# EPCU.net
KiCad netlist of a schematic drawn in Altium Designer
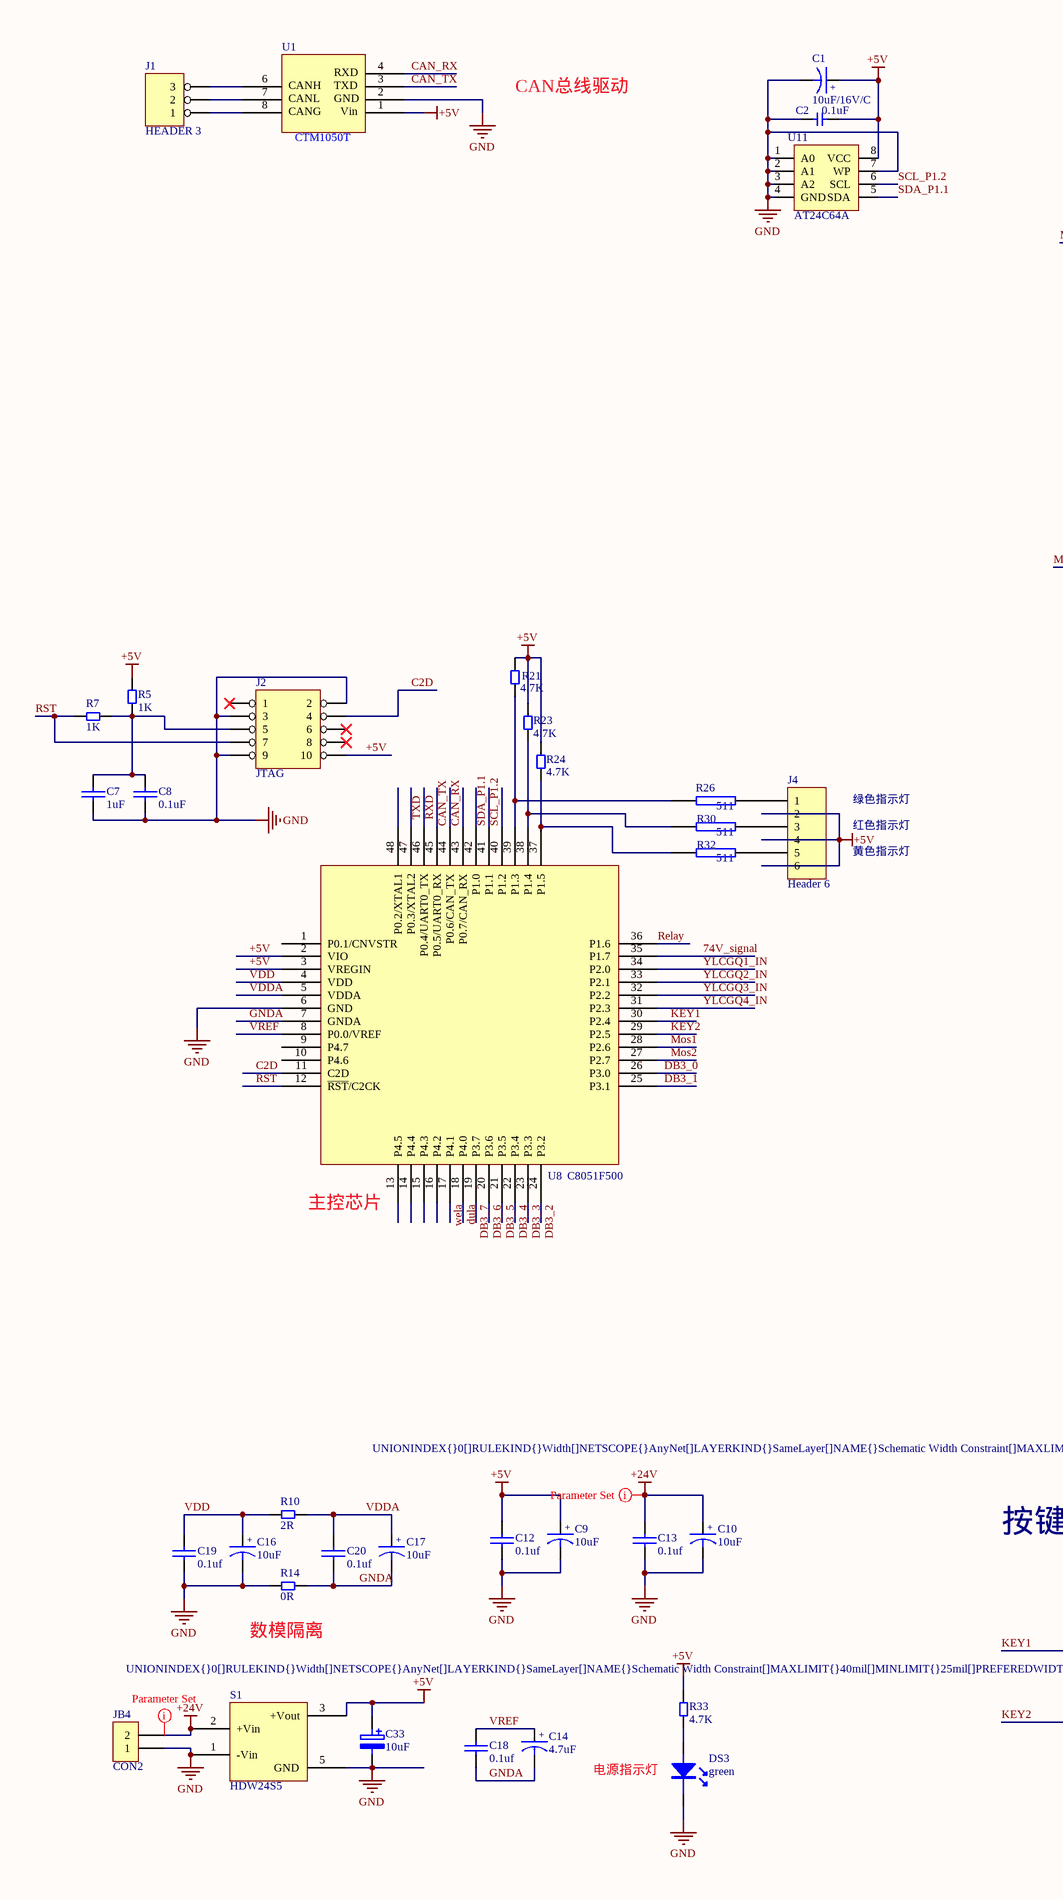
[diagram p0: EPCU.SchDoc, left]
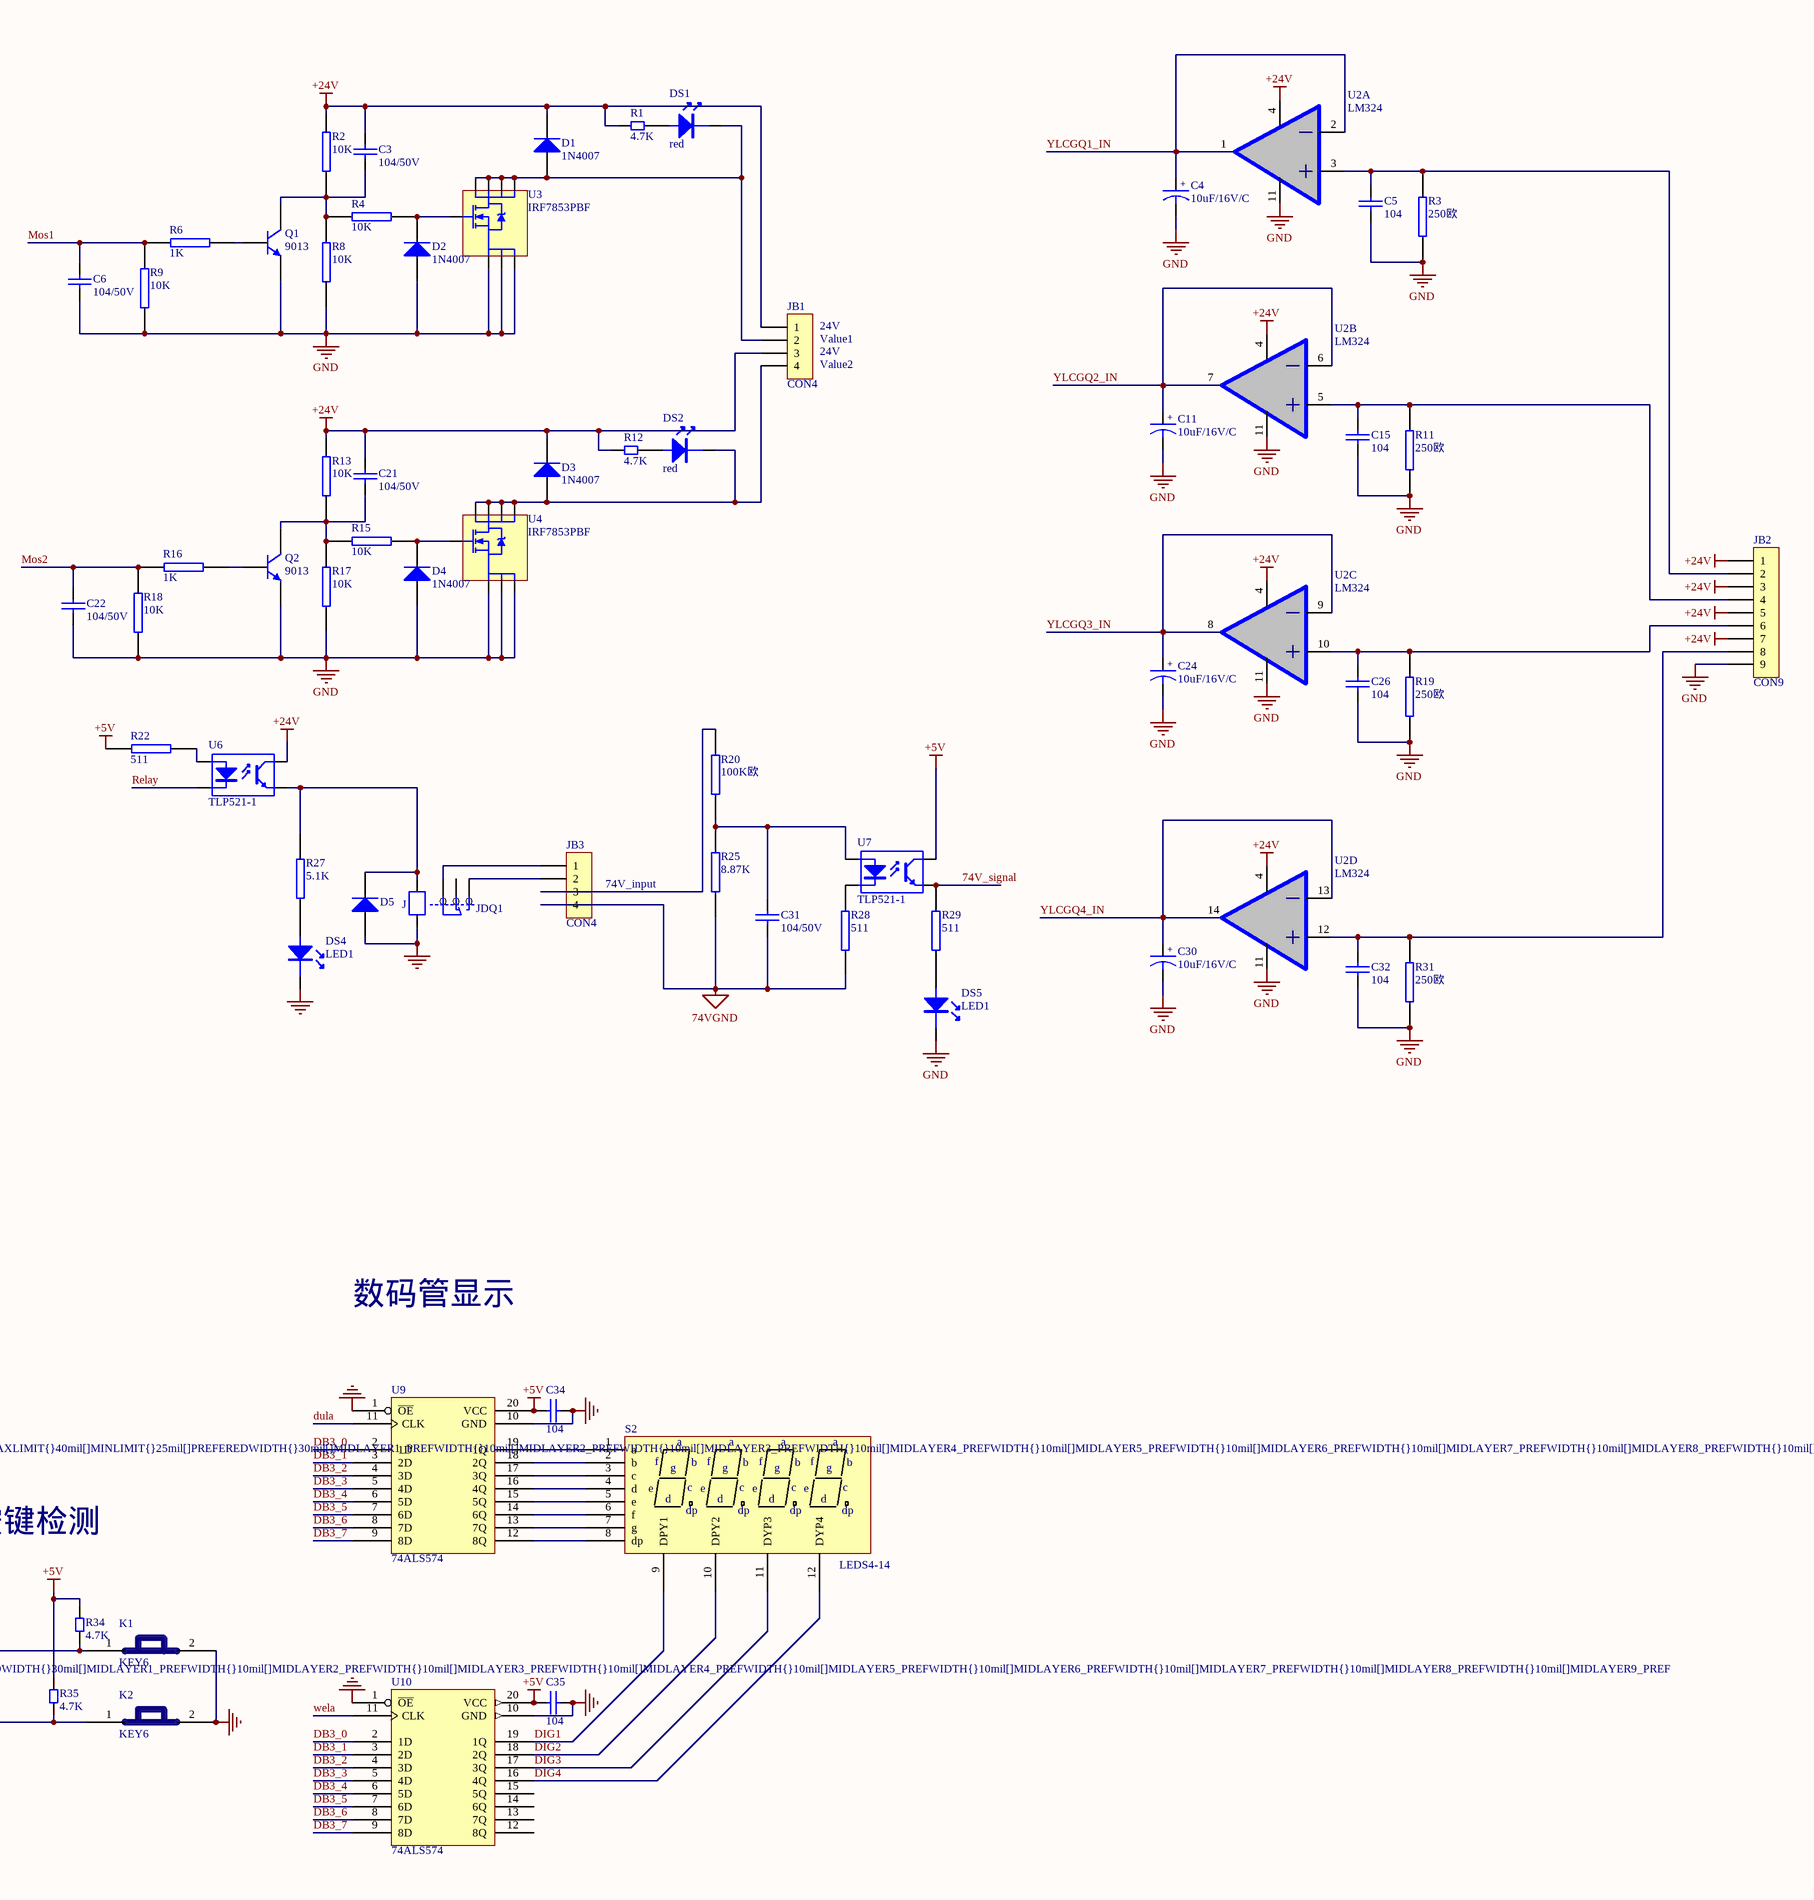
[diagram p1: EPCU.SchDoc, right]

(export (version "E")
  (design (tool "Eeschema 10.0.6"))
  (components
    (comp (ref "C1")
      (value "10uF/16V/C")
      (footprint "106E")
      (description "Capacitor")
      (libsource (lib "Backup of 13.02.20 XBX-APXSIRBASE4(change int0 and t2ex)") (part "CAPACITOR POL"))
    )
    (comp (ref "C2") (value "0.1uF") (footprint "0805") (libsource (lib "*") (part "CAP_S")))
    (comp (ref "C3")
      (value "104/50V")
      (footprint "0805")
      (description "Capacitor")
      (libsource (lib "PIS_JINAN") (part "CAP"))
    )
    (comp (ref "C4")
      (value "10uF/16V/C")
      (footprint "106E")
      (description "Capacitor")
      (libsource (lib "Backup of 13.02.20 XBX-APXSIRBASE4(change int0 and t2ex)") (part "CAPACITOR POL"))
    )
    (comp (ref "C5")
      (value "104")
      (footprint "0805")
      (description "Capacitor")
      (libsource (lib "PIS_JINAN") (part "CAP"))
    )
    (comp (ref "C6")
      (value "104/50V")
      (footprint "0805")
      (description "Capacitor")
      (libsource (lib "PIS_JINAN") (part "CAP"))
    )
    (comp (ref "C7")
      (value "1uF")
      (footprint "0805")
      (description "Capacitor")
      (libsource (lib "Backup of XBX-LINK") (part "CAP"))
    )
    (comp (ref "C8")
      (value "0.1uF")
      (footprint "0805")
      (description "Capacitor")
      (libsource (lib "Backup of XBX-LINK") (part "CAP"))
    )
    (comp (ref "C9")
      (value "10uF")
      (footprint "106E")
      (description "Capacitor")
      (libsource (lib "Backup of 13.02.20 XBX-APXSIRBASE4(change int0 and t2ex)") (part "CAPACITOR POL"))
    )
    (comp (ref "C10")
      (value "10uF")
      (footprint "106E")
      (description "Capacitor")
      (libsource (lib "Backup of 13.02.20 XBX-APXSIRBASE4(change int0 and t2ex)") (part "CAPACITOR POL"))
    )
    (comp (ref "C11")
      (value "10uF/16V/C")
      (footprint "106E")
      (description "Capacitor")
      (libsource (lib "Backup of 13.02.20 XBX-APXSIRBASE4(change int0 and t2ex)") (part "CAPACITOR POL"))
    )
    (comp (ref "C12")
      (value "0.1uf")
      (footprint "0805")
      (description "Capacitor")
      (libsource (lib "Backup of XBX-LINK") (part "CAP"))
    )
    (comp (ref "C13")
      (value "0.1uf")
      (footprint "0805")
      (description "Capacitor")
      (libsource (lib "Backup of XBX-LINK") (part "CAP"))
    )
    (comp (ref "C14")
      (value "4.7uF")
      (footprint "106E")
      (description "Capacitor")
      (libsource (lib "Backup of 13.02.20 XBX-APXSIRBASE4(change int0 and t2ex)") (part "CAPACITOR POL"))
    )
    (comp (ref "C15")
      (value "104")
      (footprint "0805")
      (description "Capacitor")
      (libsource (lib "PIS_JINAN") (part "CAP"))
    )
    (comp (ref "C16")
      (value "10uF")
      (footprint "106E")
      (description "Capacitor")
      (libsource (lib "Backup of 13.02.20 XBX-APXSIRBASE4(change int0 and t2ex)") (part "CAPACITOR POL"))
    )
    (comp (ref "C17")
      (value "10uF")
      (footprint "106E")
      (description "Capacitor")
      (libsource (lib "Backup of 13.02.20 XBX-APXSIRBASE4(change int0 and t2ex)") (part "CAPACITOR POL"))
    )
    (comp (ref "C18")
      (value "0.1uf")
      (footprint "0805")
      (description "Capacitor")
      (libsource (lib "Backup of XBX-LINK") (part "CAP"))
    )
    (comp (ref "C19")
      (value "0.1uf")
      (footprint "0805")
      (description "Capacitor")
      (libsource (lib "Backup of XBX-LINK") (part "CAP"))
    )
    (comp (ref "C20")
      (value "0.1uf")
      (footprint "0805")
      (description "Capacitor")
      (libsource (lib "Backup of XBX-LINK") (part "CAP"))
    )
    (comp (ref "C21")
      (value "104/50V")
      (footprint "0805")
      (description "Capacitor")
      (libsource (lib "PIS_JINAN") (part "CAP"))
    )
    (comp (ref "C22")
      (value "104/50V")
      (footprint "0805")
      (description "Capacitor")
      (libsource (lib "PIS_JINAN") (part "CAP"))
    )
    (comp (ref "C24")
      (value "10uF/16V/C")
      (footprint "106E")
      (description "Capacitor")
      (libsource (lib "Backup of 13.02.20 XBX-APXSIRBASE4(change int0 and t2ex)") (part "CAPACITOR POL"))
    )
    (comp (ref "C26")
      (value "104")
      (footprint "0805")
      (description "Capacitor")
      (libsource (lib "PIS_JINAN") (part "CAP"))
    )
    (comp (ref "C30")
      (value "10uF/16V/C")
      (footprint "106E")
      (description "Capacitor")
      (libsource (lib "Backup of 13.02.20 XBX-APXSIRBASE4(change int0 and t2ex)") (part "CAPACITOR POL"))
    )
    (comp (ref "C31")
      (value "104/50V")
      (footprint "0805")
      (description "Capacitor")
      (libsource (lib "PIS_JINAN") (part "CAP"))
    )
    (comp (ref "C32")
      (value "104")
      (footprint "0805")
      (description "Capacitor")
      (libsource (lib "PIS_JINAN") (part "CAP"))
    )
    (comp (ref "C33") (value "10uF") (footprint "RB.2/.4") (libsource (lib "*") (part "Pro12.tmp_22uF_5")))
    (comp (ref "C34")
      (value "104")
      (footprint "0805")
      (description "Capacitor")
      (libsource (lib "*") (part "CAP"))
    )
    (comp (ref "C35")
      (value "104")
      (footprint "0805")
      (description "Capacitor")
      (libsource (lib "*") (part "CAP"))
    )
    (comp (ref "D1")
      (value "1N4007")
      (footprint "DO-41")
      (description "1 Amp General Purpose Rectifier")
      (fields (field (name "PUBLISHER") "Altium Limited"))
      (libsource (lib "Miscellaneous Devices") (part "Diode 1N4007"))
    )
    (comp (ref "D2")
      (value "1N4007")
      (footprint "DO-41")
      (description "1 Amp General Purpose Rectifier")
      (fields (field (name "PUBLISHER") "Altium Limited"))
      (libsource (lib "Miscellaneous Devices") (part "Diode 1N4007"))
    )
    (comp (ref "D3")
      (value "1N4007")
      (footprint "DO-41")
      (description "1 Amp General Purpose Rectifier")
      (fields (field (name "PUBLISHER") "Altium Limited"))
      (libsource (lib "Miscellaneous Devices") (part "Diode 1N4007"))
    )
    (comp (ref "D4")
      (value "1N4007")
      (footprint "DO-41")
      (description "1 Amp General Purpose Rectifier")
      (fields (field (name "PUBLISHER") "Altium Limited"))
      (libsource (lib "Miscellaneous Devices") (part "Diode 1N4007"))
    )
    (comp (ref "D5")
      (value "Diode 1N4001")
      (footprint "DO-41")
      (description "1 Amp General Purpose Rectifier")
      (fields (field (name "PUBLISHER") "Altium Limited"))
      (libsource (lib "Miscellaneous Devices") (part "Diode 1N4001"))
    )
    (comp (ref "DS1") (value "red") (footprint "1206DIODE") (libsource (lib "Documents") (part "LED")))
    (comp (ref "DS2") (value "red") (footprint "1206DIODE") (libsource (lib "Documents") (part "LED")))
    (comp (ref "DS3") (value "green") (footprint "1206DIODE") (libsource (lib "Documents") (part "LED")))
    (comp (ref "DS4")
      (value "LED1")
      (footprint "1206DIODE")
      (description "1206")
      (libsource (lib "csu") (part "LED"))
    )
    (comp (ref "DS5")
      (value "LED1")
      (footprint "1206DIODE")
      (description "1206")
      (libsource (lib "csu") (part "LED"))
    )
    (comp (ref "J1")
      (value "HEADER 3")
      (footprint "254-3")
      (libsource (lib "Backup of XBX-LINK") (part "HEADER 3"))
    )
    (comp (ref "J2")
      (value "JTAG")
      (footprint "DC3-10P")
      (libsource (lib "Backup of XBX-LINK") (part "HEADER 5X2"))
    )
    (comp (ref "J4")
      (value "Header 6")
      (footprint "HDR1X6")
      (description "Header, 6-Pin")
      (fields (field (name "PUBLISHER") "Altium Limited"))
      (libsource (lib "Miscellaneous Connectors") (part "Header 6"))
    )
    (comp (ref "JB1")
      (value "CON4")
      (footprint "SIP4")
      (description "zhijiao")
      (libsource (lib "csu") (part "CON4"))
    )
    (comp (ref "JB2")
      (value "CON9")
      (footprint "SIP9")
      (description "connector")
      (libsource (lib "csu") (part "CON9"))
    )
    (comp (ref "JB3")
      (value "CON4")
      (footprint "SIP4")
      (description "zhijiao")
      (libsource (lib "csu") (part "CON4"))
    )
    (comp (ref "JB4") (value "CON2") (footprint "POWER2") (libsource (lib "csu") (part "CON2")))
    (comp (ref "JDQ1") (value "RELAY") (footprint "jidianqi_12VDC") (libsource (lib "csu") (part "RELAY")))
    (comp (ref "K1") (value "KEY6") (footprint "KEY6") (libsource (lib "ludebo_Library1") (part "KEY6")))
    (comp (ref "K2") (value "KEY6") (footprint "KEY6") (libsource (lib "ludebo_Library1") (part "KEY6")))
    (comp (ref "Q1")
      (value "9013")
      (footprint "TO-226-AA")
      (description "NPN Bipolar Transistor")
      (fields (field (name "PUBLISHER") "Altium Limited"))
      (libsource (lib "Miscellaneous Devices") (part "NPN"))
    )
    (comp (ref "Q2")
      (value "9013")
      (footprint "TO-226-AA")
      (description "NPN Bipolar Transistor")
      (fields (field (name "PUBLISHER") "Altium Limited"))
      (libsource (lib "Miscellaneous Devices") (part "NPN"))
    )
    (comp (ref "R1") (value "4.7K") (footprint "0805") (libsource (lib "Documents") (part "RES-S")))
    (comp (ref "R2") (value "10K") (footprint "0805") (libsource (lib "PIS_JINAN") (part "RES2")))
    (comp (ref "R3") (value "250欧") (footprint "AXIAL0.4") (libsource (lib "csu") (part "RES2")))
    (comp (ref "R4") (value "10K") (footprint "0805") (libsource (lib "PIS_JINAN") (part "RES2")))
    (comp (ref "R5") (value "1K") (footprint "0805") (libsource (lib "Backup of XBX-LINK") (part "RES-S")))
    (comp (ref "R6") (value "1K") (footprint "0805") (libsource (lib "PIS_JINAN") (part "RES2")))
    (comp (ref "R7") (value "1K") (footprint "0805") (libsource (lib "Backup of XBX-LINK") (part "RES-S")))
    (comp (ref "R8") (value "10K") (footprint "0805") (libsource (lib "PIS_JINAN") (part "RES2")))
    (comp (ref "R9") (value "10K") (footprint "0805") (libsource (lib "PIS_JINAN") (part "RES2")))
    (comp (ref "R10") (value "2R") (footprint "0805") (libsource (lib "Documents") (part "RES-S")))
    (comp (ref "R11") (value "250欧") (footprint "AXIAL0.4") (libsource (lib "csu") (part "RES2")))
    (comp (ref "R12") (value "4.7K") (footprint "0805") (libsource (lib "Documents") (part "RES-S")))
    (comp (ref "R13") (value "10K") (footprint "0805") (libsource (lib "PIS_JINAN") (part "RES2")))
    (comp (ref "R14") (value "0R") (footprint "0805") (libsource (lib "Documents") (part "RES-S")))
    (comp (ref "R15") (value "10K") (footprint "0805") (libsource (lib "PIS_JINAN") (part "RES2")))
    (comp (ref "R16") (value "1K") (footprint "0805") (libsource (lib "PIS_JINAN") (part "RES2")))
    (comp (ref "R17") (value "10K") (footprint "0805") (libsource (lib "PIS_JINAN") (part "RES2")))
    (comp (ref "R18") (value "10K") (footprint "0805") (libsource (lib "PIS_JINAN") (part "RES2")))
    (comp (ref "R19") (value "250欧") (footprint "AXIAL0.4") (libsource (lib "csu") (part "RES2")))
    (comp (ref "R20") (value "100K欧") (footprint "AXIAL0.4") (libsource (lib "csu") (part "RES2")))
    (comp (ref "R21") (value "4.7K") (footprint "0805") (libsource (lib "Documents") (part "RES-S")))
    (comp (ref "R22") (value "511") (footprint "0805") (libsource (lib "PIS_JINAN") (part "RES2")))
    (comp (ref "R23") (value "4.7K") (footprint "0805") (libsource (lib "Documents") (part "RES-S")))
    (comp (ref "R24") (value "4.7K") (footprint "0805") (libsource (lib "Documents") (part "RES-S")))
    (comp (ref "R25") (value "8.87K") (footprint "AXIAL0.4") (libsource (lib "csu") (part "RES2")))
    (comp (ref "R26") (value "511") (footprint "0805") (libsource (lib "PIS_JINAN") (part "RES2")))
    (comp (ref "R27") (value "5.1K") (footprint "0805") (libsource (lib "PIS_JINAN") (part "RES2")))
    (comp (ref "R28") (value "511") (footprint "0805") (libsource (lib "PIS_JINAN") (part "RES2")))
    (comp (ref "R29") (value "511") (footprint "1206DIODE") (libsource (lib "PIS_JINAN") (part "RES2")))
    (comp (ref "R30") (value "511") (footprint "0805") (libsource (lib "PIS_JINAN") (part "RES2")))
    (comp (ref "R31") (value "250欧") (footprint "AXIAL0.4") (libsource (lib "csu") (part "RES2")))
    (comp (ref "R32") (value "511") (footprint "0805") (libsource (lib "PIS_JINAN") (part "RES2")))
    (comp (ref "R33") (value "4.7K") (footprint "0805") (libsource (lib "Documents") (part "RES-S")))
    (comp (ref "R34") (value "4.7K") (footprint "0805") (libsource (lib "Documents") (part "RES-S")))
    (comp (ref "R35") (value "4.7K") (footprint "0805") (libsource (lib "Documents") (part "RES-S")))
    (comp (ref "S1") (value "HDW24S5") (footprint "HDW24S5") (libsource (lib "csu") (part "HDW24S5")))
    (comp (ref "S2")
      (value "LEDS4-14")
      (footprint "LEDS4-14")
      (libsource (lib "ludebo_Library1") (part "LEDS4-14"))
    )
    (comp (ref "U1") (value "~") (footprint "CYM1050T") (libsource (lib "csu") (part "CTM1050T")))
    (comp (ref "U2") (value "LM324") (footprint "lm324") (libsource (lib "csu") (part "LM324")))
    (comp (ref "U3") (value "IRF7853PBF") (footprint "SOP-8") (libsource (lib "csu") (part "IRF7853PBF")))
    (comp (ref "U4") (value "IRF7853PBF") (footprint "SO-8") (libsource (lib "csu") (part "IRF7853PBF")))
    (comp (ref "U6") (value "TLP521-1") (footprint "TLP521-1") (libsource (lib "csu") (part "TLP521-1")))
    (comp (ref "U7") (value "TLP521-1") (footprint "TLP521-1") (libsource (lib "csu") (part "TLP521-1")))
    (comp (ref "U8")
      (value "C8051F500")
      (footprint "TQFP-48")
      (libsource (lib "Backup of XBX-LINK") (part "C8051F500/1/4/5"))
    )
    (comp (ref "U9") (value "74ALS574") (footprint "SOL-20") (libsource (lib "*") (part "74ALS574")))
    (comp (ref "U10") (value "74ALS574") (footprint "SOL-20") (libsource (lib "*") (part "74ALS574")))
    (comp (ref "U11") (value "AT24C64A") (footprint "SO-8") (libsource (lib "*") (part "AT24CXXA")))
  )
  (nets
    (net (code "1") (name "+5V") (class "Default")
      (node (ref "C1") (pin "1") (pinfunction "1_1") (pintype "passive"))
      (node (ref "C12") (pin "2") (pinfunction "2_2") (pintype "passive"))
      (node (ref "C2") (pin "2") (pinfunction "2_2") (pintype "passive"))
      (node (ref "C33") (pin "1") (pintype "passive"))
      (node (ref "C34") (pin "1") (pinfunction "1_1") (pintype "passive"))
      (node (ref "C35") (pin "1") (pinfunction "1_1") (pintype "passive"))
      (node (ref "C9") (pin "1") (pinfunction "1_1") (pintype "passive"))
      (node (ref "J2") (pin "10") (pinfunction "10_10") (pintype "passive"))
      (node (ref "J4") (pin "2") (pinfunction "2_2") (pintype "passive"))
      (node (ref "J4") (pin "4") (pinfunction "4_4") (pintype "passive"))
      (node (ref "J4") (pin "6") (pinfunction "6_6") (pintype "passive"))
      (node (ref "R21") (pin "2") (pinfunction "2_2") (pintype "passive"))
      (node (ref "R22") (pin "2") (pinfunction "2_2") (pintype "passive"))
      (node (ref "R23") (pin "1") (pinfunction "1_1") (pintype "passive"))
      (node (ref "R24") (pin "1") (pinfunction "1_1") (pintype "passive"))
      (node (ref "R33") (pin "1") (pinfunction "1_1") (pintype "passive"))
      (node (ref "R34") (pin "1") (pinfunction "1_1") (pintype "passive"))
      (node (ref "R35") (pin "2") (pinfunction "2_2") (pintype "passive"))
      (node (ref "R5") (pin "1") (pinfunction "1_1") (pintype "passive"))
      (node (ref "S1") (pin "3") (pinfunction "+Vout_3") (pintype "passive"))
      (node (ref "U1") (pin "1") (pinfunction "1_1") (pintype "passive"))
      (node (ref "U10") (pin "20") (pinfunction "VCC_20") (pintype "output"))
      (node (ref "U11") (pin "8") (pinfunction "VCC_8") (pintype "passive"))
      (node (ref "U7") (pin "4") (pinfunction "C_4") (pintype "passive"))
      (node (ref "U8") (pin "2") (pinfunction "VIO_2") (pintype "passive"))
      (node (ref "U8") (pin "3") (pinfunction "VREGIN_3") (pintype "passive"))
      (node (ref "U9") (pin "20") (pinfunction "VCC_20") (pintype "output"))
    )
    (net (code "2") (name "+24V") (class "Default")
      (node (ref "C10") (pin "1") (pinfunction "1_1") (pintype "passive"))
      (node (ref "C13") (pin "2") (pinfunction "2_2") (pintype "passive"))
      (node (ref "C21") (pin "1") (pinfunction "1_1") (pintype "passive"))
      (node (ref "C3") (pin "1") (pinfunction "1_1") (pintype "passive"))
      (node (ref "D1") (pin "2") (pinfunction "K_2") (pintype "passive"))
      (node (ref "D3") (pin "2") (pinfunction "K_2") (pintype "passive"))
      (node (ref "JB1") (pin "1") (pinfunction "1_1") (pintype "passive"))
      (node (ref "JB1") (pin "3") (pinfunction "3_3") (pintype "passive"))
      (node (ref "JB2") (pin "1") (pinfunction "1_1") (pintype "passive"))
      (node (ref "JB2") (pin "3") (pinfunction "3_3") (pintype "passive"))
      (node (ref "JB2") (pin "5") (pinfunction "5_5") (pintype "passive"))
      (node (ref "JB2") (pin "7") (pinfunction "7_7") (pintype "passive"))
      (node (ref "JB4") (pin "2") (pinfunction "2_2") (pintype "passive"))
      (node (ref "R1") (pin "2") (pinfunction "2_2") (pintype "passive"))
      (node (ref "R12") (pin "2") (pinfunction "2_2") (pintype "passive"))
      (node (ref "R13") (pin "2") (pinfunction "2_2") (pintype "passive"))
      (node (ref "R2") (pin "2") (pinfunction "2_2") (pintype "passive"))
      (node (ref "S1") (pin "2") (pinfunction "+Vin_2") (pintype "passive"))
      (node (ref "U2") (pin "4") (pinfunction "4_4") (pintype "passive"))
      (node (ref "U6") (pin "4") (pinfunction "C_4") (pintype "passive"))
    )
    (net (code "3") (name "/74V_signal") (class "Default")
      (node (ref "R29") (pin "2") (pinfunction "2_2") (pintype "passive"))
      (node (ref "U7") (pin "3") (pinfunction "E_3") (pintype "passive"))
      (node (ref "U8") (pin "35") (pinfunction "P1.7_35") (pintype "passive"))
    )
    (net (code "4") (name "/C2D") (class "Default")
      (node (ref "J2") (pin "4") (pinfunction "4_4") (pintype "passive"))
      (node (ref "U8") (pin "11") (pinfunction "C2D_11") (pintype "passive"))
    )
    (net (code "5") (name "/CAN_RX") (class "Default")
      (node (ref "U1") (pin "4") (pinfunction "4_4") (pintype "passive"))
      (node (ref "U8") (pin "43") (pinfunction "P0.7/CAN_RX_43") (pintype "passive"))
    )
    (net (code "6") (name "/CAN_TX") (class "Default")
      (node (ref "U1") (pin "3") (pinfunction "3_3") (pintype "passive"))
      (node (ref "U8") (pin "44") (pinfunction "P0.6/CAN_TX_44") (pintype "passive"))
    )
    (net (code "7") (name "/DB3_0") (class "Default")
      (node (ref "U10") (pin "2") (pinfunction "1D_2") (pintype "passive"))
      (node (ref "U8") (pin "26") (pinfunction "P3.0_26") (pintype "passive"))
      (node (ref "U9") (pin "2") (pinfunction "1D_2") (pintype "passive"))
    )
    (net (code "8") (name "/DB3_1") (class "Default")
      (node (ref "U10") (pin "3") (pinfunction "2D_3") (pintype "passive"))
      (node (ref "U8") (pin "25") (pinfunction "P3.1_25") (pintype "passive"))
      (node (ref "U9") (pin "3") (pinfunction "2D_3") (pintype "passive"))
    )
    (net (code "9") (name "/DB3_2") (class "Default")
      (node (ref "U10") (pin "4") (pinfunction "3D_4") (pintype "passive"))
      (node (ref "U8") (pin "24") (pinfunction "P3.2_24") (pintype "passive"))
      (node (ref "U9") (pin "4") (pinfunction "3D_4") (pintype "passive"))
    )
    (net (code "10") (name "/DB3_3") (class "Default")
      (node (ref "U10") (pin "5") (pinfunction "4D_5") (pintype "passive"))
      (node (ref "U8") (pin "23") (pinfunction "P3.3_23") (pintype "passive"))
      (node (ref "U9") (pin "5") (pinfunction "4D_5") (pintype "passive"))
    )
    (net (code "11") (name "/DB3_4") (class "Default")
      (node (ref "U10") (pin "6") (pinfunction "5D_6") (pintype "passive"))
      (node (ref "U8") (pin "22") (pinfunction "P3.4_22") (pintype "passive"))
      (node (ref "U9") (pin "6") (pinfunction "5D_6") (pintype "passive"))
    )
    (net (code "12") (name "/DB3_5") (class "Default")
      (node (ref "U10") (pin "7") (pinfunction "6D_7") (pintype "passive"))
      (node (ref "U8") (pin "21") (pinfunction "P3.5_21") (pintype "passive"))
      (node (ref "U9") (pin "7") (pinfunction "6D_7") (pintype "passive"))
    )
    (net (code "13") (name "/DB3_6") (class "Default")
      (node (ref "U10") (pin "8") (pinfunction "7D_8") (pintype "passive"))
      (node (ref "U8") (pin "20") (pinfunction "P3.6_20") (pintype "passive"))
      (node (ref "U9") (pin "8") (pinfunction "7D_8") (pintype "passive"))
    )
    (net (code "14") (name "/DB3_7") (class "Default")
      (node (ref "U10") (pin "9") (pinfunction "8D_9") (pintype "passive"))
      (node (ref "U8") (pin "19") (pinfunction "P3.7_19") (pintype "passive"))
      (node (ref "U9") (pin "9") (pinfunction "8D_9") (pintype "passive"))
    )
    (net (code "15") (name "/DIG1") (class "Default")
      (node (ref "S2") (pin "9") (pinfunction "DPY1_9") (pintype "passive"))
      (node (ref "U10") (pin "19") (pinfunction "1Q_19") (pintype "passive"))
    )
    (net (code "16") (name "/DIG2") (class "Default")
      (node (ref "S2") (pin "10") (pinfunction "DPY2_10") (pintype "passive"))
      (node (ref "U10") (pin "18") (pinfunction "2Q_18") (pintype "passive"))
    )
    (net (code "17") (name "/DIG3") (class "Default")
      (node (ref "S2") (pin "11") (pinfunction "DYP3_11") (pintype "passive"))
      (node (ref "U10") (pin "17") (pinfunction "3Q_17") (pintype "passive"))
    )
    (net (code "18") (name "/DIG4") (class "Default")
      (node (ref "S2") (pin "12") (pinfunction "DYP4_12") (pintype "passive"))
      (node (ref "U10") (pin "16") (pinfunction "4Q_16") (pintype "passive"))
    )
    (net (code "19") (name "/GNDA") (class "Default")
      (node (ref "C14") (pin "2") (pinfunction "2_2") (pintype "passive"))
      (node (ref "C17") (pin "2") (pinfunction "2_2") (pintype "passive"))
      (node (ref "C18") (pin "1") (pinfunction "1_1") (pintype "passive"))
      (node (ref "C20") (pin "1") (pinfunction "1_1") (pintype "passive"))
      (node (ref "R14") (pin "1") (pinfunction "1_1") (pintype "passive"))
      (node (ref "U8") (pin "7") (pinfunction "GNDA_7") (pintype "passive"))
    )
    (net (code "20") (name "/KEY1") (class "Default")
      (node (ref "K1") (pin "1") (pinfunction "1_1") (pintype "passive"))
      (node (ref "R34") (pin "2") (pinfunction "2_2") (pintype "passive"))
      (node (ref "U8") (pin "30") (pinfunction "P2.4_30") (pintype "passive"))
    )
    (net (code "21") (name "/KEY2") (class "Default")
      (node (ref "K2") (pin "1") (pinfunction "1_1") (pintype "passive"))
      (node (ref "R35") (pin "1") (pinfunction "1_1") (pintype "passive"))
      (node (ref "U8") (pin "29") (pinfunction "P2.5_29") (pintype "passive"))
    )
    (net (code "22") (name "/Mos1") (class "Default")
      (node (ref "C6") (pin "1") (pinfunction "1_1") (pintype "passive"))
      (node (ref "R6") (pin "1") (pinfunction "1_1") (pintype "passive"))
      (node (ref "R9") (pin "2") (pinfunction "2_2") (pintype "passive"))
      (node (ref "U8") (pin "28") (pinfunction "P2.6_28") (pintype "passive"))
    )
    (net (code "23") (name "/Mos2") (class "Default")
      (node (ref "C22") (pin "1") (pinfunction "1_1") (pintype "passive"))
      (node (ref "R16") (pin "1") (pinfunction "1_1") (pintype "passive"))
      (node (ref "R18") (pin "2") (pinfunction "2_2") (pintype "passive"))
      (node (ref "U8") (pin "27") (pinfunction "P2.7_27") (pintype "passive"))
    )
    (net (code "24") (name "/RST") (class "Default")
      (node (ref "J2") (pin "7") (pinfunction "7_7") (pintype "passive"))
      (node (ref "R7") (pin "2") (pinfunction "2_2") (pintype "passive"))
      (node (ref "U8") (pin "12") (pinfunction "~{RST}/C2CK_12") (pintype "passive"))
    )
    (net (code "25") (name "/RXD") (class "Default")
      (node (ref "U8") (pin "45") (pinfunction "P0.5/UART0_RX_45") (pintype "passive"))
    )
    (net (code "26") (name "/Relay") (class "Default")
      (node (ref "U6") (pin "2") (pinfunction "K_2") (pintype "passive"))
      (node (ref "U8") (pin "36") (pinfunction "P1.6_36") (pintype "passive"))
    )
    (net (code "27") (name "/SCL_P1.2") (class "Default")
      (node (ref "U11") (pin "6") (pinfunction "SCL_6") (pintype "passive"))
      (node (ref "U8") (pin "40") (pinfunction "P1.2_40") (pintype "passive"))
    )
    (net (code "28") (name "/SDA_P1.1") (class "Default")
      (node (ref "U11") (pin "5") (pinfunction "SDA_5") (pintype "passive"))
      (node (ref "U8") (pin "41") (pinfunction "P1.1_41") (pintype "passive"))
    )
    (net (code "29") (name "/TXD") (class "Default")
      (node (ref "U8") (pin "46") (pinfunction "P0.4/UART0_TX_46") (pintype "passive"))
    )
    (net (code "30") (name "/VDD") (class "Default")
      (node (ref "C16") (pin "1") (pinfunction "1_1") (pintype "passive"))
      (node (ref "C19") (pin "2") (pinfunction "2_2") (pintype "passive"))
      (node (ref "R10") (pin "2") (pinfunction "2_2") (pintype "passive"))
      (node (ref "U8") (pin "4") (pinfunction "VDD_4") (pintype "passive"))
    )
    (net (code "31") (name "/VDDA") (class "Default")
      (node (ref "C17") (pin "1") (pinfunction "1_1") (pintype "passive"))
      (node (ref "C20") (pin "2") (pinfunction "2_2") (pintype "passive"))
      (node (ref "R10") (pin "1") (pinfunction "1_1") (pintype "passive"))
      (node (ref "U8") (pin "5") (pinfunction "VDDA_5") (pintype "passive"))
    )
    (net (code "32") (name "/VREF") (class "Default")
      (node (ref "C14") (pin "1") (pinfunction "1_1") (pintype "passive"))
      (node (ref "C18") (pin "2") (pinfunction "2_2") (pintype "passive"))
      (node (ref "U8") (pin "8") (pinfunction "P0.0/VREF_8") (pintype "passive"))
    )
    (net (code "33") (name "/YLCGQ1_IN") (class "Default")
      (node (ref "C4") (pin "1") (pinfunction "1_1") (pintype "passive"))
      (node (ref "U2") (pin "1") (pinfunction "1_1") (pintype "passive"))
      (node (ref "U2") (pin "2") (pinfunction "2_2") (pintype "passive"))
      (node (ref "U8") (pin "34") (pinfunction "P2.0_34") (pintype "passive"))
    )
    (net (code "34") (name "/YLCGQ2_IN") (class "Default")
      (node (ref "C11") (pin "1") (pinfunction "1_1") (pintype "passive"))
      (node (ref "U2") (pin "6") (pinfunction "6_6") (pintype "passive"))
      (node (ref "U2") (pin "7") (pinfunction "7_7") (pintype "passive"))
      (node (ref "U8") (pin "33") (pinfunction "P2.1_33") (pintype "passive"))
    )
    (net (code "35") (name "/YLCGQ3_IN") (class "Default")
      (node (ref "C24") (pin "1") (pinfunction "1_1") (pintype "passive"))
      (node (ref "U2") (pin "8") (pinfunction "8_8") (pintype "passive"))
      (node (ref "U2") (pin "9") (pinfunction "9_9") (pintype "passive"))
      (node (ref "U8") (pin "32") (pinfunction "P2.2_32") (pintype "passive"))
    )
    (net (code "36") (name "/YLCGQ4_IN") (class "Default")
      (node (ref "C30") (pin "1") (pinfunction "1_1") (pintype "passive"))
      (node (ref "U2") (pin "13") (pinfunction "13_13") (pintype "passive"))
      (node (ref "U2") (pin "14") (pinfunction "14_14") (pintype "passive"))
      (node (ref "U8") (pin "31") (pinfunction "P2.3_31") (pintype "passive"))
    )
    (net (code "37") (name "/dula") (class "Default")
      (node (ref "U8") (pin "18") (pinfunction "P4.0_18") (pintype "passive"))
      (node (ref "U9") (pin "11") (pinfunction "CLK_11") (pintype "passive"))
    )
    (net (code "38") (name "/wela") (class "Default")
      (node (ref "U10") (pin "11") (pinfunction "CLK_11") (pintype "passive"))
      (node (ref "U8") (pin "17") (pinfunction "P4.1_17") (pintype "passive"))
    )
    (net (code "39") (name "74VGND") (class "Default")
      (node (ref "C31") (pin "2") (pinfunction "2_2") (pintype "passive"))
      (node (ref "JB3") (pin "4") (pinfunction "4_4") (pintype "passive"))
      (node (ref "R25") (pin "1") (pinfunction "1_1") (pintype "passive"))
      (node (ref "R28") (pin "2") (pinfunction "2_2") (pintype "passive"))
    )
    (net (code "40") (name "GND") (class "Default")
      (node (ref "C1") (pin "2") (pinfunction "2_2") (pintype "passive"))
      (node (ref "C10") (pin "2") (pinfunction "2_2") (pintype "passive"))
      (node (ref "C11") (pin "2") (pinfunction "2_2") (pintype "passive"))
      (node (ref "C12") (pin "1") (pinfunction "1_1") (pintype "passive"))
      (node (ref "C13") (pin "1") (pinfunction "1_1") (pintype "passive"))
      (node (ref "C15") (pin "2") (pinfunction "2_2") (pintype "passive"))
      (node (ref "C16") (pin "2") (pinfunction "2_2") (pintype "passive"))
      (node (ref "C19") (pin "1") (pinfunction "1_1") (pintype "passive"))
      (node (ref "C2") (pin "1") (pinfunction "1_1") (pintype "passive"))
      (node (ref "C22") (pin "2") (pinfunction "2_2") (pintype "passive"))
      (node (ref "C24") (pin "2") (pinfunction "2_2") (pintype "passive"))
      (node (ref "C26") (pin "2") (pinfunction "2_2") (pintype "passive"))
      (node (ref "C30") (pin "2") (pinfunction "2_2") (pintype "passive"))
      (node (ref "C32") (pin "2") (pinfunction "2_2") (pintype "passive"))
      (node (ref "C33") (pin "2") (pintype "passive"))
      (node (ref "C34") (pin "2") (pinfunction "2_2") (pintype "passive"))
      (node (ref "C35") (pin "2") (pinfunction "2_2") (pintype "passive"))
      (node (ref "C4") (pin "2") (pinfunction "2_2") (pintype "passive"))
      (node (ref "C5") (pin "2") (pinfunction "2_2") (pintype "passive"))
      (node (ref "C6") (pin "2") (pinfunction "2_2") (pintype "passive"))
      (node (ref "C7") (pin "1") (pinfunction "1_1") (pintype "passive"))
      (node (ref "C8") (pin "1") (pinfunction "1_1") (pintype "passive"))
      (node (ref "C9") (pin "2") (pinfunction "2_2") (pintype "passive"))
      (node (ref "D2") (pin "1") (pinfunction "A_1") (pintype "passive"))
      (node (ref "D4") (pin "1") (pinfunction "A_1") (pintype "passive"))
      (node (ref "D5") (pin "1") (pinfunction "A_1") (pintype "passive"))
      (node (ref "DS3") (pin "2") (pinfunction "K_2") (pintype "passive"))
      (node (ref "DS4") (pin "2") (pinfunction "K_2") (pintype "passive"))
      (node (ref "DS5") (pin "2") (pinfunction "K_2") (pintype "passive"))
      (node (ref "J2") (pin "2") (pinfunction "2_2") (pintype "passive"))
      (node (ref "J2") (pin "3") (pinfunction "3_3") (pintype "passive"))
      (node (ref "J2") (pin "9") (pinfunction "9_9") (pintype "passive"))
      (node (ref "JB2") (pin "9") (pinfunction "9_9") (pintype "passive"))
      (node (ref "JB4") (pin "1") (pinfunction "1_1") (pintype "passive"))
      (node (ref "JDQ1") (pin "2") (pintype "passive"))
      (node (ref "K1") (pin "2") (pinfunction "2_2") (pintype "passive"))
      (node (ref "K2") (pin "2") (pinfunction "2_2") (pintype "passive"))
      (node (ref "Q1") (pin "1") (pinfunction "E_1") (pintype "passive"))
      (node (ref "Q2") (pin "1") (pinfunction "E_1") (pintype "passive"))
      (node (ref "R11") (pin "2") (pinfunction "2_2") (pintype "passive"))
      (node (ref "R14") (pin "2") (pinfunction "2_2") (pintype "passive"))
      (node (ref "R17") (pin "1") (pinfunction "1_1") (pintype "passive"))
      (node (ref "R18") (pin "1") (pinfunction "1_1") (pintype "passive"))
      (node (ref "R19") (pin "2") (pinfunction "2_2") (pintype "passive"))
      (node (ref "R3") (pin "2") (pinfunction "2_2") (pintype "passive"))
      (node (ref "R31") (pin "2") (pinfunction "2_2") (pintype "passive"))
      (node (ref "R8") (pin "1") (pinfunction "1_1") (pintype "passive"))
      (node (ref "R9") (pin "1") (pinfunction "1_1") (pintype "passive"))
      (node (ref "S1") (pin "1") (pinfunction "-Vin_1") (pintype "passive"))
      (node (ref "S1") (pin "5") (pinfunction "GND_5") (pintype "passive"))
      (node (ref "U1") (pin "2") (pinfunction "2_2") (pintype "passive"))
      (node (ref "U10") (pin "1") (pinfunction "~{OE}_1") (pintype "passive"))
      (node (ref "U10") (pin "10") (pinfunction "GND_10") (pintype "output"))
      (node (ref "U11") (pin "1") (pinfunction "A0_1") (pintype "passive"))
      (node (ref "U11") (pin "2") (pinfunction "A1_2") (pintype "passive"))
      (node (ref "U11") (pin "3") (pinfunction "A2_3") (pintype "passive"))
      (node (ref "U11") (pin "4") (pinfunction "GND_4") (pintype "passive"))
      (node (ref "U11") (pin "7") (pinfunction "WP_7") (pintype "passive"))
      (node (ref "U2") (pin "11") (pinfunction "11_11") (pintype "passive"))
      (node (ref "U3") (pin "1") (pinfunction "S_1") (pintype "passive"))
      (node (ref "U3") (pin "2") (pinfunction "S_2") (pintype "passive"))
      (node (ref "U3") (pin "3") (pinfunction "S_3") (pintype "passive"))
      (node (ref "U4") (pin "1") (pinfunction "S_1") (pintype "passive"))
      (node (ref "U4") (pin "2") (pinfunction "S_2") (pintype "passive"))
      (node (ref "U4") (pin "3") (pinfunction "S_3") (pintype "passive"))
      (node (ref "U8") (pin "6") (pinfunction "GND_6") (pintype "passive"))
      (node (ref "U9") (pin "1") (pinfunction "~{OE}_1") (pintype "passive"))
      (node (ref "U9") (pin "10") (pinfunction "GND_10") (pintype "output"))
    )
    (net (code "41") (name "Net-(C5-Pad1)") (class "Default")
      (node (ref "C5") (pin "1") (pinfunction "1_1") (pintype "passive"))
      (node (ref "JB2") (pin "2") (pinfunction "2_2") (pintype "passive"))
      (node (ref "R3") (pin "1") (pinfunction "1_1") (pintype "passive"))
      (node (ref "U2") (pin "3") (pinfunction "3_3") (pintype "passive"))
    )
    (net (code "42") (name "Net-(C7-Pad2)") (class "Default")
      (node (ref "C7") (pin "2") (pinfunction "2_2") (pintype "passive"))
      (node (ref "C8") (pin "2") (pinfunction "2_2") (pintype "passive"))
      (node (ref "J2") (pin "5") (pinfunction "5_5") (pintype "passive"))
      (node (ref "R5") (pin "2") (pinfunction "2_2") (pintype "passive"))
      (node (ref "R7") (pin "1") (pinfunction "1_1") (pintype "passive"))
    )
    (net (code "43") (name "Net-(C15-Pad1)") (class "Default")
      (node (ref "C15") (pin "1") (pinfunction "1_1") (pintype "passive"))
      (node (ref "JB2") (pin "4") (pinfunction "4_4") (pintype "passive"))
      (node (ref "R11") (pin "1") (pinfunction "1_1") (pintype "passive"))
      (node (ref "U2") (pin "5") (pinfunction "5_5") (pintype "passive"))
    )
    (net (code "44") (name "Net-(C26-Pad1)") (class "Default")
      (node (ref "C26") (pin "1") (pinfunction "1_1") (pintype "passive"))
      (node (ref "JB2") (pin "6") (pinfunction "6_6") (pintype "passive"))
      (node (ref "R19") (pin "1") (pinfunction "1_1") (pintype "passive"))
      (node (ref "U2") (pin "10") (pinfunction "10_10") (pintype "passive"))
    )
    (net (code "45") (name "Net-(C32-Pad1)") (class "Default")
      (node (ref "C32") (pin "1") (pinfunction "1_1") (pintype "passive"))
      (node (ref "JB2") (pin "8") (pinfunction "8_8") (pintype "passive"))
      (node (ref "R31") (pin "1") (pinfunction "1_1") (pintype "passive"))
      (node (ref "U2") (pin "12") (pinfunction "12_12") (pintype "passive"))
    )
    (net (code "46") (name "Net-(D1-A)") (class "Default")
      (node (ref "D1") (pin "1") (pinfunction "A_1") (pintype "passive"))
      (node (ref "DS1") (pin "2") (pinfunction "K_2") (pintype "passive"))
      (node (ref "JB1") (pin "2") (pinfunction "2_2") (pintype "passive"))
      (node (ref "U3") (pin "5") (pinfunction "D_5") (pintype "passive"))
      (node (ref "U3") (pin "6") (pinfunction "D_6") (pintype "passive"))
      (node (ref "U3") (pin "7") (pinfunction "D_7") (pintype "passive"))
      (node (ref "U3") (pin "8") (pinfunction "D_8") (pintype "passive"))
    )
    (net (code "47") (name "Net-(D2-K)") (class "Default")
      (node (ref "D2") (pin "2") (pinfunction "K_2") (pintype "passive"))
      (node (ref "R4") (pin "1") (pinfunction "1_1") (pintype "passive"))
      (node (ref "U3") (pin "4") (pinfunction "G_4") (pintype "passive"))
    )
    (net (code "48") (name "Net-(D3-A)") (class "Default")
      (node (ref "D3") (pin "1") (pinfunction "A_1") (pintype "passive"))
      (node (ref "DS2") (pin "2") (pinfunction "K_2") (pintype "passive"))
      (node (ref "JB1") (pin "4") (pinfunction "4_4") (pintype "passive"))
      (node (ref "U4") (pin "5") (pinfunction "D_5") (pintype "passive"))
      (node (ref "U4") (pin "6") (pinfunction "D_6") (pintype "passive"))
      (node (ref "U4") (pin "7") (pinfunction "D_7") (pintype "passive"))
      (node (ref "U4") (pin "8") (pinfunction "D_8") (pintype "passive"))
    )
    (net (code "49") (name "Net-(D4-K)") (class "Default")
      (node (ref "D4") (pin "2") (pinfunction "K_2") (pintype "passive"))
      (node (ref "R15") (pin "1") (pinfunction "1_1") (pintype "passive"))
      (node (ref "U4") (pin "4") (pinfunction "G_4") (pintype "passive"))
    )
    (net (code "50") (name "Net-(D5-K)") (class "Default")
      (node (ref "D5") (pin "2") (pinfunction "K_2") (pintype "passive"))
      (node (ref "JDQ1") (pin "5") (pintype "passive"))
      (node (ref "R27") (pin "2") (pinfunction "2_2") (pintype "passive"))
      (node (ref "U6") (pin "3") (pinfunction "E_3") (pintype "passive"))
    )
    (net (code "51") (name "Net-(DS1-A)") (class "Default")
      (node (ref "DS1") (pin "1") (pinfunction "A_1") (pintype "passive"))
      (node (ref "R1") (pin "1") (pinfunction "1_1") (pintype "passive"))
    )
    (net (code "52") (name "Net-(DS2-A)") (class "Default")
      (node (ref "DS2") (pin "1") (pinfunction "A_1") (pintype "passive"))
      (node (ref "R12") (pin "1") (pinfunction "1_1") (pintype "passive"))
    )
    (net (code "53") (name "Net-(DS3-A)") (class "Default")
      (node (ref "DS3") (pin "1") (pinfunction "A_1") (pintype "passive"))
      (node (ref "R33") (pin "2") (pinfunction "2_2") (pintype "passive"))
    )
    (net (code "54") (name "Net-(DS4-A)") (class "Default")
      (node (ref "DS4") (pin "1") (pinfunction "A_1") (pintype "passive"))
      (node (ref "R27") (pin "1") (pinfunction "1_1") (pintype "passive"))
    )
    (net (code "55") (name "Net-(DS5-A)") (class "Default")
      (node (ref "DS5") (pin "1") (pinfunction "A_1") (pintype "passive"))
      (node (ref "R29") (pin "1") (pinfunction "1_1") (pintype "passive"))
    )
    (net (code "56") (name "Net-(J1-Pad1)") (class "Default")
      (node (ref "J1") (pin "1") (pinfunction "1_1") (pintype "passive"))
      (node (ref "U1") (pin "8") (pinfunction "8_8") (pintype "passive"))
    )
    (net (code "57") (name "Net-(J1-Pad2)") (class "Default")
      (node (ref "J1") (pin "2") (pinfunction "2_2") (pintype "passive"))
      (node (ref "U1") (pin "7") (pinfunction "7_7") (pintype "passive"))
    )
    (net (code "58") (name "Net-(J1-Pad3)") (class "Default")
      (node (ref "J1") (pin "3") (pinfunction "3_3") (pintype "passive"))
      (node (ref "U1") (pin "6") (pinfunction "6_6") (pintype "passive"))
    )
    (net (code "59") (name "Net-(J4-Pad1)") (class "Default")
      (node (ref "J4") (pin "1") (pinfunction "1_1") (pintype "passive"))
      (node (ref "R26") (pin "1") (pinfunction "1_1") (pintype "passive"))
    )
    (net (code "60") (name "Net-(J4-Pad3)") (class "Default")
      (node (ref "J4") (pin "3") (pinfunction "3_3") (pintype "passive"))
      (node (ref "R30") (pin "1") (pinfunction "1_1") (pintype "passive"))
    )
    (net (code "61") (name "Net-(J4-Pad5)") (class "Default")
      (node (ref "J4") (pin "5") (pinfunction "5_5") (pintype "passive"))
      (node (ref "R32") (pin "1") (pinfunction "1_1") (pintype "passive"))
    )
    (net (code "62") (name "Net-(JB3-Pad1)") (class "Default")
      (node (ref "JB3") (pin "1") (pinfunction "1_1") (pintype "passive"))
      (node (ref "JDQ1") (pin "1") (pintype "passive"))
    )
    (net (code "63") (name "Net-(JB3-Pad2)") (class "Default")
      (node (ref "JB3") (pin "2") (pinfunction "2_2") (pintype "passive"))
      (node (ref "JDQ1") (pin "3") (pintype "passive"))
    )
    (net (code "64") (name "Net-(JB3-Pad3)") (class "Default")
      (node (ref "JB3") (pin "3") (pinfunction "3_3") (pintype "passive"))
      (node (ref "R20") (pin "2") (pinfunction "2_2") (pintype "passive"))
    )
    (net (code "65") (name "Net-(Q1-B)") (class "Default")
      (node (ref "Q1") (pin "2") (pinfunction "B_2") (pintype "passive"))
      (node (ref "R6") (pin "2") (pinfunction "2_2") (pintype "passive"))
    )
    (net (code "66") (name "Net-(Q1-C)") (class "Default")
      (node (ref "C3") (pin "2") (pinfunction "2_2") (pintype "passive"))
      (node (ref "Q1") (pin "3") (pinfunction "C_3") (pintype "passive"))
      (node (ref "R2") (pin "1") (pinfunction "1_1") (pintype "passive"))
      (node (ref "R4") (pin "2") (pinfunction "2_2") (pintype "passive"))
      (node (ref "R8") (pin "2") (pinfunction "2_2") (pintype "passive"))
    )
    (net (code "67") (name "Net-(Q2-B)") (class "Default")
      (node (ref "Q2") (pin "2") (pinfunction "B_2") (pintype "passive"))
      (node (ref "R16") (pin "2") (pinfunction "2_2") (pintype "passive"))
    )
    (net (code "68") (name "Net-(Q2-C)") (class "Default")
      (node (ref "C21") (pin "2") (pinfunction "2_2") (pintype "passive"))
      (node (ref "Q2") (pin "3") (pinfunction "C_3") (pintype "passive"))
      (node (ref "R13") (pin "1") (pinfunction "1_1") (pintype "passive"))
      (node (ref "R15") (pin "2") (pinfunction "2_2") (pintype "passive"))
      (node (ref "R17") (pin "2") (pinfunction "2_2") (pintype "passive"))
    )
    (net (code "69") (name "Net-(S2-a)") (class "Default")
      (node (ref "S2") (pin "1") (pinfunction "a_1") (pintype "passive"))
      (node (ref "U9") (pin "19") (pinfunction "1Q_19") (pintype "passive"))
    )
    (net (code "70") (name "Net-(S2-b)") (class "Default")
      (node (ref "S2") (pin "2") (pinfunction "b_2") (pintype "passive"))
      (node (ref "U9") (pin "18") (pinfunction "2Q_18") (pintype "passive"))
    )
    (net (code "71") (name "Net-(S2-c)") (class "Default")
      (node (ref "S2") (pin "3") (pinfunction "c_3") (pintype "passive"))
      (node (ref "U9") (pin "17") (pinfunction "3Q_17") (pintype "passive"))
    )
    (net (code "72") (name "Net-(S2-d)") (class "Default")
      (node (ref "S2") (pin "4") (pinfunction "d_4") (pintype "passive"))
      (node (ref "U9") (pin "16") (pinfunction "4Q_16") (pintype "passive"))
    )
    (net (code "73") (name "Net-(S2-dp)") (class "Default")
      (node (ref "S2") (pin "8") (pinfunction "dp_8") (pintype "passive"))
      (node (ref "U9") (pin "12") (pinfunction "8Q_12") (pintype "passive"))
    )
    (net (code "74") (name "Net-(S2-e)") (class "Default")
      (node (ref "S2") (pin "5") (pinfunction "e_5") (pintype "passive"))
      (node (ref "U9") (pin "15") (pinfunction "5Q_15") (pintype "passive"))
    )
    (net (code "75") (name "Net-(S2-f)") (class "Default")
      (node (ref "S2") (pin "6") (pinfunction "f_6") (pintype "passive"))
      (node (ref "U9") (pin "14") (pinfunction "6Q_14") (pintype "passive"))
    )
    (net (code "76") (name "Net-(S2-g)") (class "Default")
      (node (ref "S2") (pin "7") (pinfunction "g_7") (pintype "passive"))
      (node (ref "U9") (pin "13") (pinfunction "7Q_13") (pintype "passive"))
    )
    (net (code "77") (name "Net-(U6-A)") (class "Default")
      (node (ref "R22") (pin "1") (pinfunction "1_1") (pintype "passive"))
      (node (ref "U6") (pin "1") (pinfunction "A_1") (pintype "passive"))
    )
    (net (code "78") (name "Net-(U7-A)") (class "Default")
      (node (ref "C31") (pin "1") (pinfunction "1_1") (pintype "passive"))
      (node (ref "R20") (pin "1") (pinfunction "1_1") (pintype "passive"))
      (node (ref "R25") (pin "2") (pinfunction "2_2") (pintype "passive"))
      (node (ref "U7") (pin "1") (pinfunction "A_1") (pintype "passive"))
    )
    (net (code "79") (name "Net-(U7-K)") (class "Default")
      (node (ref "R28") (pin "1") (pinfunction "1_1") (pintype "passive"))
      (node (ref "U7") (pin "2") (pinfunction "K_2") (pintype "passive"))
    )
    (net (code "80") (name "Net-(U8-P1.3)") (class "Default")
      (node (ref "R21") (pin "1") (pinfunction "1_1") (pintype "passive"))
      (node (ref "R26") (pin "2") (pinfunction "2_2") (pintype "passive"))
      (node (ref "U8") (pin "39") (pinfunction "P1.3_39") (pintype "passive"))
    )
    (net (code "81") (name "Net-(U8-P1.4)") (class "Default")
      (node (ref "R23") (pin "2") (pinfunction "2_2") (pintype "passive"))
      (node (ref "R30") (pin "2") (pinfunction "2_2") (pintype "passive"))
      (node (ref "U8") (pin "38") (pinfunction "P1.4_38") (pintype "passive"))
    )
    (net (code "82") (name "Net-(U8-P1.5)") (class "Default")
      (node (ref "R24") (pin "2") (pinfunction "2_2") (pintype "passive"))
      (node (ref "R32") (pin "2") (pinfunction "2_2") (pintype "passive"))
      (node (ref "U8") (pin "37") (pinfunction "P1.5_37") (pintype "passive"))
    )
    (net (code "83") (name "unconnected-(J2-Pad1)") (class "Default")
      (node (ref "J2") (pin "1") (pinfunction "1_1") (pintype "passive+no_connect"))
    )
    (net (code "84") (name "unconnected-(J2-Pad6)") (class "Default")
      (node (ref "J2") (pin "6") (pinfunction "6_6") (pintype "passive+no_connect"))
    )
    (net (code "85") (name "unconnected-(J2-Pad8)") (class "Default")
      (node (ref "J2") (pin "8") (pinfunction "8_8") (pintype "passive+no_connect"))
    )
    (net (code "86") (name "unconnected-(JDQ1-Pad4)") (class "Default")
      (node (ref "JDQ1") (pin "4") (pintype "passive"))
    )
    (net (code "87") (name "unconnected-(U8-P0.1{slash}CNVSTR-Pad1)") (class "Default")
      (node (ref "U8") (pin "1") (pinfunction "P0.1/CNVSTR_1") (pintype "passive"))
    )
    (net (code "88") (name "unconnected-(U8-P0.2{slash}XTAL1-Pad48)") (class "Default")
      (node (ref "U8") (pin "48") (pinfunction "P0.2/XTAL1_48") (pintype "passive"))
    )
    (net (code "89") (name "unconnected-(U8-P0.3{slash}XTAL2-Pad47)") (class "Default")
      (node (ref "U8") (pin "47") (pinfunction "P0.3/XTAL2_47") (pintype "passive"))
    )
    (net (code "90") (name "unconnected-(U8-P1.0-Pad42)") (class "Default")
      (node (ref "U8") (pin "42") (pinfunction "P1.0_42") (pintype "passive"))
    )
    (net (code "91") (name "unconnected-(U8-P4.2-Pad16)") (class "Default")
      (node (ref "U8") (pin "16") (pinfunction "P4.2_16") (pintype "passive"))
    )
    (net (code "92") (name "unconnected-(U8-P4.3-Pad15)") (class "Default")
      (node (ref "U8") (pin "15") (pinfunction "P4.3_15") (pintype "passive"))
    )
    (net (code "93") (name "unconnected-(U8-P4.4-Pad14)") (class "Default")
      (node (ref "U8") (pin "14") (pinfunction "P4.4_14") (pintype "passive"))
    )
    (net (code "94") (name "unconnected-(U8-P4.5-Pad13)") (class "Default")
      (node (ref "U8") (pin "13") (pinfunction "P4.5_13") (pintype "passive"))
    )
    (net (code "95") (name "unconnected-(U8-P4.6-Pad10)") (class "Default")
      (node (ref "U8") (pin "10") (pinfunction "P4.6_10") (pintype "passive"))
    )
    (net (code "96") (name "unconnected-(U8-P4.7-Pad9)") (class "Default")
      (node (ref "U8") (pin "9") (pinfunction "P4.7_9") (pintype "passive"))
    )
    (net (code "97") (name "unconnected-(U10-5Q-Pad15)") (class "Default")
      (node (ref "U10") (pin "15") (pinfunction "5Q_15") (pintype "passive"))
    )
    (net (code "98") (name "unconnected-(U10-6Q-Pad14)") (class "Default")
      (node (ref "U10") (pin "14") (pinfunction "6Q_14") (pintype "passive"))
    )
    (net (code "99") (name "unconnected-(U10-7Q-Pad13)") (class "Default")
      (node (ref "U10") (pin "13") (pinfunction "7Q_13") (pintype "passive"))
    )
    (net (code "100") (name "unconnected-(U10-8Q-Pad12)") (class "Default")
      (node (ref "U10") (pin "12") (pinfunction "8Q_12") (pintype "passive"))
    )
  )
)
